# POWER.net
KiCad netlist of a schematic drawn in Altium Designer
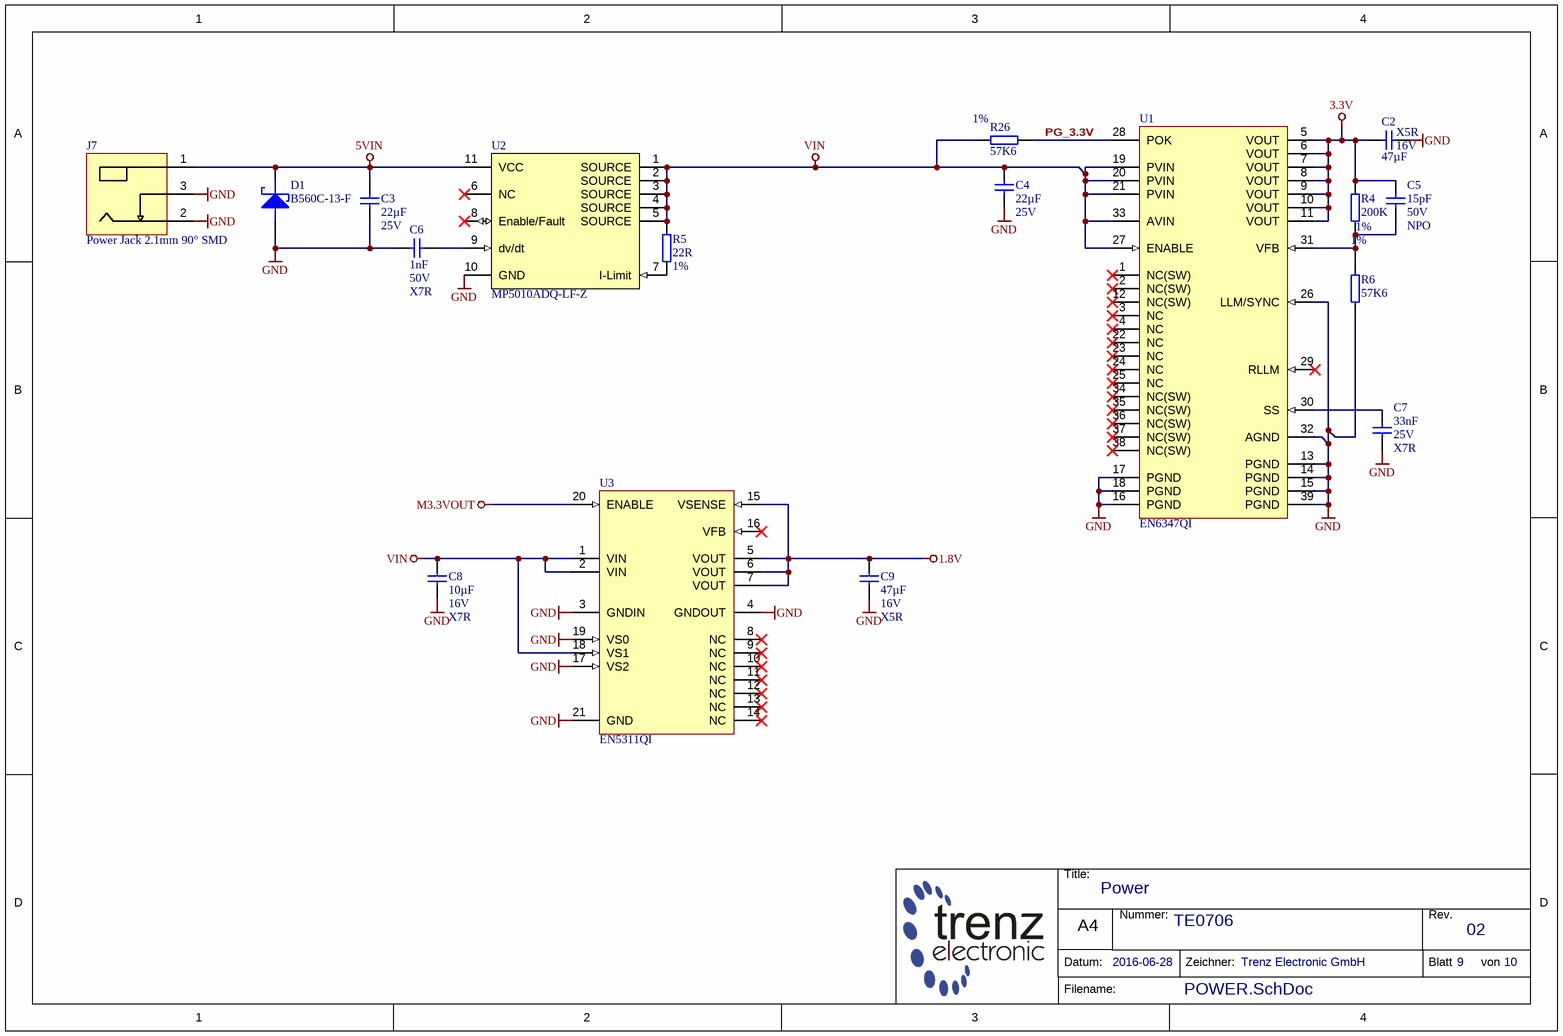
[diagram p0: POWER.SchDoc]

(export (version "E")
  (design (tool "Eeschema 10.0.6"))
  (components
    (comp (ref "C2")
      (value "47µF")
      (footprint "CAPC3216X180N")
      (description "KON 47µF 16V  X5R SMD 20%")
      (fields
        (field (name "VOLTAGE") "16V")
        (field (name "TECHNOLOGY") "X5R")
        (field (name "TOLERANCE") "20%")
      )
      (libsource (lib "TE") (part "CAP-NP"))
    )
    (comp (ref "C3")
      (value "22µF")
      (footprint "CAPC3216X180N")
      (description "KON 22µF X5R 25V SMD 10%")
      (fields (field (name "VOLTAGE") "25V") (field (name "TOLERANCE") "10%"))
      (libsource (lib "TE") (part "CAP-NP"))
    )
    (comp (ref "C4")
      (value "22µF")
      (footprint "CAPC3216X180N")
      (description "KON 22µF X5R 25V SMD 10%")
      (fields (field (name "VOLTAGE") "25V") (field (name "TOLERANCE") "10%"))
      (libsource (lib "TE") (part "CAP-NP"))
    )
    (comp (ref "C5")
      (value "15pF")
      (footprint "CAPC1005X55N")
      (description "KON 15pF NPO 50V SMD")
      (fields (field (name "VOLTAGE") "50V") (field (name "TECHNOLOGY") "NPO"))
      (libsource (lib "TE") (part "CAP-NP"))
    )
    (comp (ref "C6")
      (value "1nF")
      (footprint "CAPC1005X55N")
      (description "KON 1nF 50V X7R SMD")
      (fields
        (field (name "VOLTAGE") "50V")
        (field (name "TECHNOLOGY") "X7R")
        (field (name "TOLERANCE") "10%")
      )
      (libsource (lib "TE") (part "CAP-NP"))
    )
    (comp (ref "C7")
      (value "33nF")
      (footprint "CAPC1005X55N")
      (description "KON 33nF 25V X7R SMD")
      (fields (field (name "VOLTAGE") "25V") (field (name "TECHNOLOGY") "X7R"))
      (libsource (lib "TE") (part "CAP-NP"))
    )
    (comp (ref "C8")
      (value "10µF")
      (footprint "CAPC2012X135N")
      (description "KON 10µF 16V X7R SMD 10%")
      (fields
        (field (name "VOLTAGE") "16V")
        (field (name "TECHNOLOGY") "X7R")
        (field (name "TOLERANCE") "10%")
      )
      (libsource (lib "TE") (part "CAP-NP"))
    )
    (comp (ref "C9")
      (value "47µF")
      (footprint "CAPC3216X180N")
      (description "KON 47µF 16V  X5R SMD 20%")
      (fields
        (field (name "VOLTAGE") "16V")
        (field (name "TECHNOLOGY") "X5R")
        (field (name "TOLERANCE") "20%")
      )
      (libsource (lib "TE") (part "CAP-NP"))
    )
    (comp (ref "D1")
      (value "B560C-13-F")
      (footprint "DIOM7959X250N")
      (description "B560C-13-F SMD")
      (libsource (lib "TE") (part "SCHOTTKY"))
    )
    (comp (ref "J7")
      (value "Power Jack 2.1mm 90° SMD")
      (footprint "694106106102")
      (libsource (lib "TE") (part "694106106102"))
    )
    (comp (ref "R4")
      (value "200K")
      (footprint "RESC1005X40N")
      (description "WID SMD 200K 1% 0,063W")
      (fields (field (name "TOLERANCE") "1%"))
      (libsource (lib "TE") (part "RES"))
    )
    (comp (ref "R5")
      (value "22R")
      (footprint "RESC1005X40N")
      (description "WID SMD 22R 1% 0,063W")
      (fields (field (name "TOLERANCE") "1%"))
      (libsource (lib "TE") (part "RES"))
    )
    (comp (ref "R6")
      (value "57K6")
      (footprint "RESC1005X40N")
      (description "WID SMD 57K6 1% 0,063W")
      (fields (field (name "TOLERANCE") "1%"))
      (libsource (lib "TE") (part "RES"))
    )
    (comp (ref "R26")
      (value "57K6")
      (footprint "RESC1005X40N")
      (description "WID SMD 57K6 1% 0,063W")
      (fields (field (name "TOLERANCE") "1%"))
      (libsource (lib "TE") (part "RES"))
    )
    (comp (ref "U1") (value "EN6347QI") (footprint "EN63xx") (libsource (lib "TE") (part "EN63xx")))
    (comp (ref "U2")
      (value "MP5010ADQ-LF-Z")
      (footprint "SON50P300X300X100-11N")
      (fields (field (name "VOLTAGE") "5V"))
      (libsource (lib "TE") (part "MP5010A"))
    )
    (comp (ref "U3") (value "EN5311QI") (footprint "EN5311QI") (libsource (lib "TE") (part "EN5311QI")))
  )
  (nets
    (net (code "1") (name "/PG_3.3V") (class "Default")
      (node (ref "R26") (pin "2") (pinfunction "2_2") (pintype "passive"))
      (node (ref "U1") (pin "28") (pinfunction "POK_28") (pintype "open_collector"))
    )
    (net (code "2") (name "1.8V") (class "Default")
      (node (ref "C9") (pin "1") (pinfunction "1_1") (pintype "passive"))
      (node (ref "U3") (pin "15") (pinfunction "VSENSE_15") (pintype "input"))
      (node (ref "U3") (pin "5") (pinfunction "VOUT_5") (pintype "power_in"))
      (node (ref "U3") (pin "6") (pinfunction "VOUT_6") (pintype "power_in"))
      (node (ref "U3") (pin "7") (pinfunction "VOUT_7") (pintype "power_in"))
    )
    (net (code "3") (name "3.3V") (class "Default")
      (node (ref "C2") (pin "1") (pinfunction "1_1") (pintype "passive"))
      (node (ref "C5") (pin "1") (pinfunction "1_1") (pintype "passive"))
      (node (ref "R4") (pin "1") (pinfunction "1_1") (pintype "passive"))
      (node (ref "U1") (pin "10") (pinfunction "VOUT_10") (pintype "power_in"))
      (node (ref "U1") (pin "11") (pinfunction "VOUT_11") (pintype "power_in"))
      (node (ref "U1") (pin "5") (pinfunction "VOUT_5") (pintype "power_in"))
      (node (ref "U1") (pin "6") (pinfunction "VOUT_6") (pintype "power_in"))
      (node (ref "U1") (pin "7") (pinfunction "VOUT_7") (pintype "power_in"))
      (node (ref "U1") (pin "8") (pinfunction "VOUT_8") (pintype "power_in"))
      (node (ref "U1") (pin "9") (pinfunction "VOUT_9") (pintype "power_in"))
    )
    (net (code "4") (name "5VIN") (class "Default")
      (node (ref "C3") (pin "1") (pinfunction "1_1") (pintype "passive"))
      (node (ref "D1") (pin "1") (pinfunction "KATHODE_1") (pintype "passive"))
      (node (ref "J7") (pin "1") (pintype "passive"))
      (node (ref "U2") (pin "11") (pinfunction "VCC_11") (pintype "power_in"))
    )
    (net (code "5") (name "GND") (class "Default")
      (node (ref "C2") (pin "2") (pinfunction "2_2") (pintype "passive"))
      (node (ref "C3") (pin "2") (pinfunction "2_2") (pintype "passive"))
      (node (ref "C4") (pin "1") (pinfunction "1_1") (pintype "passive"))
      (node (ref "C6") (pin "1") (pinfunction "1_1") (pintype "passive"))
      (node (ref "C7") (pin "2") (pinfunction "2_2") (pintype "passive"))
      (node (ref "C8") (pin "2") (pinfunction "2_2") (pintype "passive"))
      (node (ref "C9") (pin "2") (pinfunction "2_2") (pintype "passive"))
      (node (ref "D1") (pin "2") (pinfunction "ANODE_2") (pintype "passive"))
      (node (ref "J7") (pin "2") (pintype "passive"))
      (node (ref "J7") (pin "3") (pintype "passive"))
      (node (ref "R6") (pin "2") (pinfunction "2_2") (pintype "passive"))
      (node (ref "U1") (pin "13") (pinfunction "PGND_13") (pintype "power_in"))
      (node (ref "U1") (pin "14") (pinfunction "PGND_14") (pintype "power_in"))
      (node (ref "U1") (pin "15") (pinfunction "PGND_15") (pintype "power_in"))
      (node (ref "U1") (pin "16") (pinfunction "PGND_16") (pintype "power_in"))
      (node (ref "U1") (pin "17") (pinfunction "PGND_17") (pintype "power_in"))
      (node (ref "U1") (pin "18") (pinfunction "PGND_18") (pintype "power_in"))
      (node (ref "U1") (pin "26") (pinfunction "LLM/SYNC_26") (pintype "input"))
      (node (ref "U1") (pin "32") (pinfunction "AGND_32") (pintype "power_in"))
      (node (ref "U1") (pin "39") (pinfunction "PGND_39") (pintype "power_in"))
      (node (ref "U2") (pin "10") (pinfunction "GND_10") (pintype "power_in"))
      (node (ref "U3") (pin "17") (pinfunction "VS2_17") (pintype "input"))
      (node (ref "U3") (pin "19") (pinfunction "VS0_19") (pintype "input"))
      (node (ref "U3") (pin "21") (pinfunction "GND_21") (pintype "power_in"))
      (node (ref "U3") (pin "3") (pinfunction "GNDIN_3") (pintype "power_in"))
      (node (ref "U3") (pin "4") (pinfunction "GNDOUT_4") (pintype "power_in"))
    )
    (net (code "6") (name "M3.3VOUT") (class "Default")
      (node (ref "U3") (pin "20") (pinfunction "ENABLE_20") (pintype "input"))
    )
    (net (code "7") (name "Net-(U1-SS)") (class "Default")
      (node (ref "C7") (pin "1") (pinfunction "1_1") (pintype "passive"))
      (node (ref "U1") (pin "30") (pinfunction "SS_30") (pintype "input"))
    )
    (net (code "8") (name "Net-(U1-VFB)") (class "Default")
      (node (ref "C5") (pin "2") (pinfunction "2_2") (pintype "passive"))
      (node (ref "R4") (pin "2") (pinfunction "2_2") (pintype "passive"))
      (node (ref "R6") (pin "1") (pinfunction "1_1") (pintype "passive"))
      (node (ref "U1") (pin "31") (pinfunction "VFB_31") (pintype "input"))
    )
    (net (code "9") (name "Net-(U2-I-Limit)") (class "Default")
      (node (ref "R5") (pin "2") (pinfunction "2_2") (pintype "passive"))
      (node (ref "U2") (pin "7") (pinfunction "I-Limit_7") (pintype "input"))
    )
    (net (code "10") (name "Net-(U2-dv{slash}dt)") (class "Default")
      (node (ref "C6") (pin "2") (pinfunction "2_2") (pintype "passive"))
      (node (ref "U2") (pin "9") (pinfunction "dv/dt_9") (pintype "input"))
    )
    (net (code "11") (name "VIN") (class "Default")
      (node (ref "C4") (pin "2") (pinfunction "2_2") (pintype "passive"))
      (node (ref "C8") (pin "1") (pinfunction "1_1") (pintype "passive"))
      (node (ref "R26") (pin "1") (pinfunction "1_1") (pintype "passive"))
      (node (ref "R5") (pin "1") (pinfunction "1_1") (pintype "passive"))
      (node (ref "U1") (pin "19") (pinfunction "PVIN_19") (pintype "power_in"))
      (node (ref "U1") (pin "20") (pinfunction "PVIN_20") (pintype "power_in"))
      (node (ref "U1") (pin "21") (pinfunction "PVIN_21") (pintype "power_in"))
      (node (ref "U1") (pin "27") (pinfunction "ENABLE_27") (pintype "input"))
      (node (ref "U1") (pin "33") (pinfunction "AVIN_33") (pintype "power_in"))
      (node (ref "U2") (pin "1") (pinfunction "SOURCE_1") (pintype "power_in"))
      (node (ref "U2") (pin "2") (pinfunction "SOURCE_2") (pintype "power_in"))
      (node (ref "U2") (pin "3") (pinfunction "SOURCE_3") (pintype "power_in"))
      (node (ref "U2") (pin "4") (pinfunction "SOURCE_4") (pintype "power_in"))
      (node (ref "U2") (pin "5") (pinfunction "SOURCE_5") (pintype "power_in"))
      (node (ref "U3") (pin "1") (pinfunction "VIN_1") (pintype "power_in"))
      (node (ref "U3") (pin "18") (pinfunction "VS1_18") (pintype "input"))
      (node (ref "U3") (pin "2") (pinfunction "VIN_2") (pintype "power_in"))
    )
    (net (code "12") (name "unconnected-(U1-NC(SW)-Pad1)") (class "Default")
      (node (ref "U1") (pin "1") (pinfunction "NC(SW)_1") (pintype "passive+no_connect"))
    )
    (net (code "13") (name "unconnected-(U1-NC(SW)-Pad2)") (class "Default")
      (node (ref "U1") (pin "2") (pinfunction "NC(SW)_2") (pintype "passive+no_connect"))
    )
    (net (code "14") (name "unconnected-(U1-NC(SW)-Pad12)") (class "Default")
      (node (ref "U1") (pin "12") (pinfunction "NC(SW)_12") (pintype "passive+no_connect"))
    )
    (net (code "15") (name "unconnected-(U1-NC(SW)-Pad34)") (class "Default")
      (node (ref "U1") (pin "34") (pinfunction "NC(SW)_34") (pintype "passive+no_connect"))
    )
    (net (code "16") (name "unconnected-(U1-NC(SW)-Pad35)") (class "Default")
      (node (ref "U1") (pin "35") (pinfunction "NC(SW)_35") (pintype "passive+no_connect"))
    )
    (net (code "17") (name "unconnected-(U1-NC(SW)-Pad36)") (class "Default")
      (node (ref "U1") (pin "36") (pinfunction "NC(SW)_36") (pintype "passive+no_connect"))
    )
    (net (code "18") (name "unconnected-(U1-NC(SW)-Pad37)") (class "Default")
      (node (ref "U1") (pin "37") (pinfunction "NC(SW)_37") (pintype "passive+no_connect"))
    )
    (net (code "19") (name "unconnected-(U1-NC(SW)-Pad38)") (class "Default")
      (node (ref "U1") (pin "38") (pinfunction "NC(SW)_38") (pintype "passive+no_connect"))
    )
    (net (code "20") (name "unconnected-(U1-NC-Pad3)") (class "Default")
      (node (ref "U1") (pin "3") (pinfunction "NC_3") (pintype "passive+no_connect"))
    )
    (net (code "21") (name "unconnected-(U1-NC-Pad4)") (class "Default")
      (node (ref "U1") (pin "4") (pinfunction "NC_4") (pintype "passive+no_connect"))
    )
    (net (code "22") (name "unconnected-(U1-NC-Pad22)") (class "Default")
      (node (ref "U1") (pin "22") (pinfunction "NC_22") (pintype "passive+no_connect"))
    )
    (net (code "23") (name "unconnected-(U1-NC-Pad23)") (class "Default")
      (node (ref "U1") (pin "23") (pinfunction "NC_23") (pintype "passive+no_connect"))
    )
    (net (code "24") (name "unconnected-(U1-NC-Pad24)") (class "Default")
      (node (ref "U1") (pin "24") (pinfunction "NC_24") (pintype "passive+no_connect"))
    )
    (net (code "25") (name "unconnected-(U1-NC-Pad25)") (class "Default")
      (node (ref "U1") (pin "25") (pinfunction "NC_25") (pintype "passive+no_connect"))
    )
    (net (code "26") (name "unconnected-(U1-RLLM-Pad29)") (class "Default")
      (node (ref "U1") (pin "29") (pinfunction "RLLM_29") (pintype "input+no_connect"))
    )
    (net (code "27") (name "unconnected-(U2-Enable{slash}Fault-Pad8)") (class "Default")
      (node (ref "U2") (pin "8") (pinfunction "Enable/Fault_8") (pintype "bidirectional+no_connect"))
    )
    (net (code "28") (name "unconnected-(U2-NC-Pad6)") (class "Default")
      (node (ref "U2") (pin "6") (pinfunction "NC_6") (pintype "passive+no_connect"))
    )
    (net (code "29") (name "unconnected-(U3-NC-Pad8)") (class "Default")
      (node (ref "U3") (pin "8") (pinfunction "NC_8") (pintype "passive+no_connect"))
    )
    (net (code "30") (name "unconnected-(U3-NC-Pad9)") (class "Default")
      (node (ref "U3") (pin "9") (pinfunction "NC_9") (pintype "passive+no_connect"))
    )
    (net (code "31") (name "unconnected-(U3-NC-Pad10)") (class "Default")
      (node (ref "U3") (pin "10") (pinfunction "NC_10") (pintype "passive+no_connect"))
    )
    (net (code "32") (name "unconnected-(U3-NC-Pad11)") (class "Default")
      (node (ref "U3") (pin "11") (pinfunction "NC_11") (pintype "passive+no_connect"))
    )
    (net (code "33") (name "unconnected-(U3-NC-Pad12)") (class "Default")
      (node (ref "U3") (pin "12") (pinfunction "NC_12") (pintype "passive+no_connect"))
    )
    (net (code "34") (name "unconnected-(U3-NC-Pad13)") (class "Default")
      (node (ref "U3") (pin "13") (pinfunction "NC_13") (pintype "passive+no_connect"))
    )
    (net (code "35") (name "unconnected-(U3-NC-Pad14)") (class "Default")
      (node (ref "U3") (pin "14") (pinfunction "NC_14") (pintype "passive+no_connect"))
    )
    (net (code "36") (name "unconnected-(U3-VFB-Pad16)") (class "Default")
      (node (ref "U3") (pin "16") (pinfunction "VFB_16") (pintype "input+no_connect"))
    )
  )
)
